# NCS_Wireless_Indicator_mcu1.net
KiCad netlist of a schematic drawn in Altium Designer
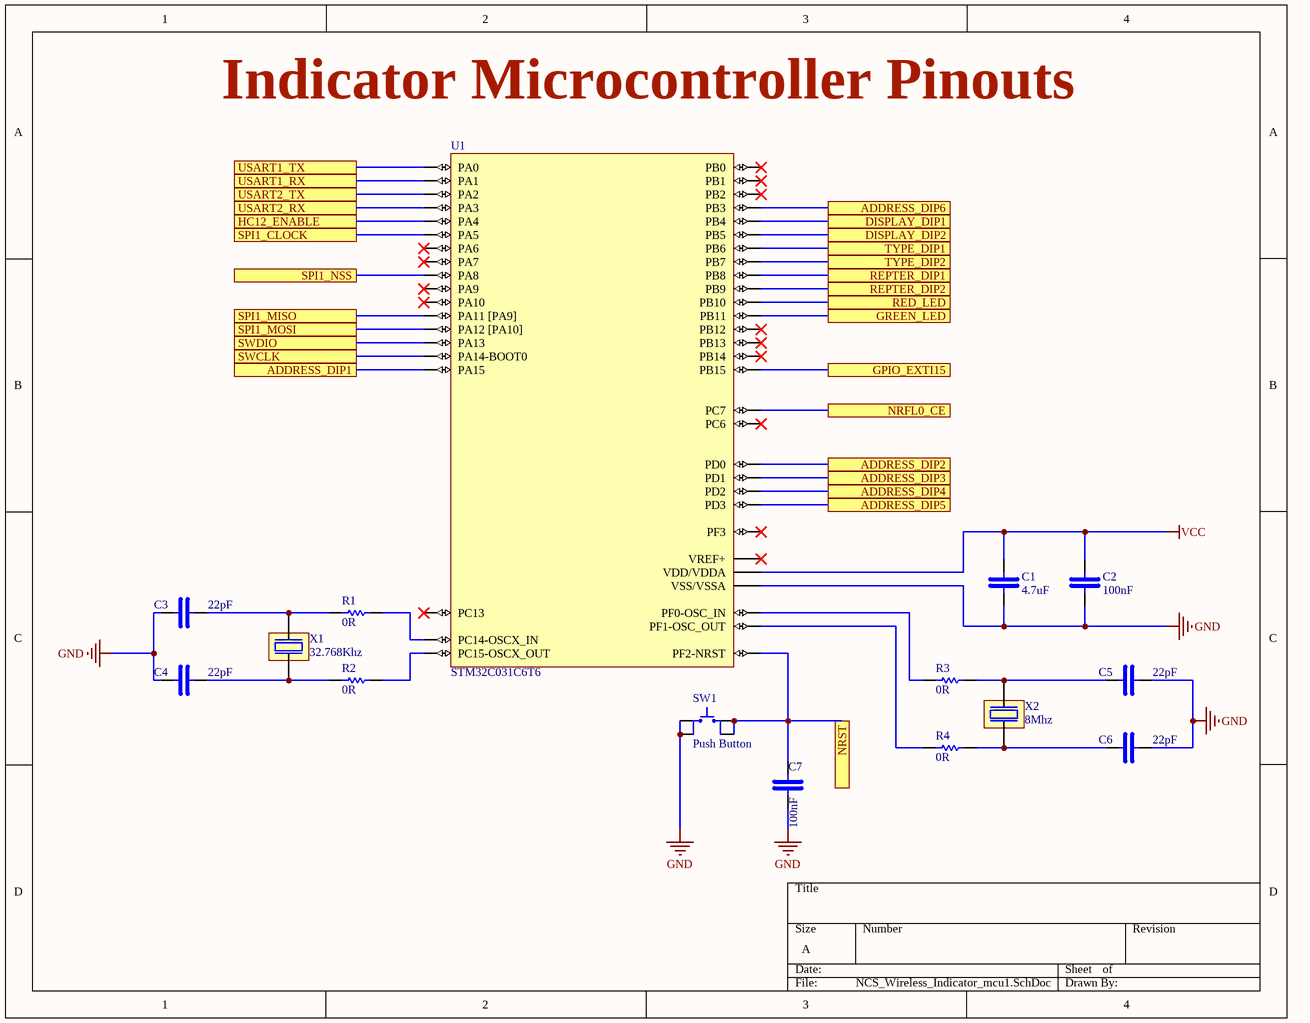
[diagram p0: NCS_Wireless_Indicator_mcu1.SchDoc]

(export (version "E")
  (design (tool "Eeschema 10.0.6"))
  (components
    (comp (ref "C1")
      (value "4.7uF")
      (footprint "C0805C209D3HACTU_2pF")
      (description "Multilayer Ceramic Capacitor, 4.7 uF, 25 V, ï¿½ 10%, X5R, 0805 [2012 Metric]")
      (fields
        (field (name "MANUFACTURER") "KEMET")
        (field (name "MANUFACTURER PART NUMBER") "C0805C475K3PACTU")
      )
      (libsource (lib "schlib") (part "C0805C475K3PACTU"))
    )
    (comp (ref "C2")
      (value "100nF")
      (footprint "C0805C104K3RACTU_100nF")
      (description "Multilayer Ceramic Capacitor, 0.1 uF, 25 V, ï¿½ 10%, X7R, 0805 [2012 Metric]")
      (fields
        (field (name "MANUFACTURER") "KEMET")
        (field (name "MANUFACTURER PART NUMBER") "C0805C104K3RACTU")
      )
      (libsource (lib "schlib") (part "C0805C104K3RACTU"))
    )
    (comp (ref "C3")
      (value "22pF")
      (footprint "C0805C209D3HACTU_2pF")
      (description "C0805C209D3HACTU_2pF")
      (fields
        (field (name "MANUFACTURER") "KEMET")
        (field (name "MANUFACTURER PART NUMBER") "C0805C209D3HACTU")
      )
      (libsource (lib "schlib") (part "C0805C209D3HACTU"))
    )
    (comp (ref "C4")
      (value "22pF")
      (footprint "C0805C209D3HACTU_2pF")
      (description "C0805C209D3HACTU_2pF")
      (fields
        (field (name "MANUFACTURER") "KEMET")
        (field (name "MANUFACTURER PART NUMBER") "C0805C209D3HACTU")
      )
      (libsource (lib "schlib") (part "C0805C209D3HACTU"))
    )
    (comp (ref "C5")
      (value "22pF")
      (footprint "C0805C209D3HACTU_2pF")
      (description "C0805C209D3HACTU_2pF")
      (fields
        (field (name "MANUFACTURER") "KEMET")
        (field (name "MANUFACTURER PART NUMBER") "C0805C209D3HACTU")
      )
      (libsource (lib "schlib") (part "C0805C209D3HACTU"))
    )
    (comp (ref "C6")
      (value "22pF")
      (footprint "C0805C209D3HACTU_2pF")
      (description "C0805C209D3HACTU_2pF")
      (fields
        (field (name "MANUFACTURER") "KEMET")
        (field (name "MANUFACTURER PART NUMBER") "C0805C209D3HACTU")
      )
      (libsource (lib "schlib") (part "C0805C209D3HACTU"))
    )
    (comp (ref "C7")
      (value "100nF")
      (footprint "C0805C104K3RACTU_100nF")
      (description "Multilayer Ceramic Capacitor, 0.1 uF, 25 V, ï¿½ 10%, X7R, 0805 [2012 Metric]")
      (fields
        (field (name "MANUFACTURER") "KEMET")
        (field (name "MANUFACTURER PART NUMBER") "C0805C104K3RACTU")
      )
      (libsource (lib "schlib") (part "C0805C104K3RACTU"))
    )
    (comp (ref "R1")
      (value "0R")
      (footprint "RC0805JR-070RL")
      (description "GENERAL PURPOSE CHIP RESISTOR Metal Glaze/thick Film, 0.125W, 0ohm, Surface Mount, 0805")
      (fields
        (field (name "MANUFACTURER") "Yageo")
        (field (name "MANUFACTURER PART NUMBER") "RC0805JR-070RL")
      )
      (libsource (lib "schlib") (part "RC0805JR-070RL"))
    )
    (comp (ref "R2")
      (value "0R")
      (footprint "RC0805JR-070RL")
      (description "GENERAL PURPOSE CHIP RESISTOR Metal Glaze/thick Film, 0.125W, 0ohm, Surface Mount, 0805")
      (fields
        (field (name "MANUFACTURER") "Yageo")
        (field (name "MANUFACTURER PART NUMBER") "RC0805JR-070RL")
      )
      (libsource (lib "schlib") (part "RC0805JR-070RL"))
    )
    (comp (ref "R3")
      (value "0R")
      (footprint "RC0805JR-070RL")
      (description "GENERAL PURPOSE CHIP RESISTOR Metal Glaze/thick Film, 0.125W, 0ohm, Surface Mount, 0805")
      (fields
        (field (name "MANUFACTURER") "Yageo")
        (field (name "MANUFACTURER PART NUMBER") "RC0805JR-070RL")
      )
      (libsource (lib "schlib") (part "RC0805JR-070RL"))
    )
    (comp (ref "R4")
      (value "0R")
      (footprint "RC0805JR-070RL")
      (description "GENERAL PURPOSE CHIP RESISTOR Metal Glaze/thick Film, 0.125W, 0ohm, Surface Mount, 0805")
      (fields
        (field (name "MANUFACTURER") "Yageo")
        (field (name "MANUFACTURER PART NUMBER") "RC0805JR-070RL")
      )
      (libsource (lib "schlib") (part "RC0805JR-070RL"))
    )
    (comp (ref "SW1")
      (value "Push Button")
      (footprint "PUSH BUTTON SMD")
      (libsource (lib "NCS_Wireless_Bed_Unit") (part "Tactile Switch SMD 4P 5.2x5.2x1.5mm - EVELTA"))
    )
    (comp (ref "U1")
      (value "STM32C031C6T6")
      (footprint "STM32C031C6T6-48N")
      (description "RISC Microcontroller, 32-Bit, FLASH, CORTEX-M4F CPU, 180MHz, CMOS, PBGA216")
      (fields (field (name "MANUFACTURER") "STMicroelectronics"))
      (libsource (lib "NCS_Wireless_Bed_Unit") (part "STM32C031C6T6"))
    )
    (comp (ref "X1")
      (value "32.768Khz")
      (footprint "32.768KHz")
      (libsource (lib "NCS_Wireless_Bed_Unit") (part "32.768 Khz RTC Crystal T38-SUNROM"))
    )
    (comp (ref "X2")
      (value "8Mhz")
      (footprint "8Mhz Crystal")
      (libsource (lib "NCS_Wireless_Bed_Unit") (part "8 Mhz Crystal HC-49US-SUNROM"))
    )
  )
  (nets
    (net (code "1") (name "/ADDRESS_DIP1") (class "Default")
      (node (ref "U1") (pin "37") (pinfunction "PA15_37") (pintype "bidirectional"))
    )
    (net (code "2") (name "/ADDRESS_DIP2") (class "Default")
      (node (ref "U1") (pin "38") (pinfunction "PD0_38") (pintype "bidirectional"))
    )
    (net (code "3") (name "/ADDRESS_DIP3") (class "Default")
      (node (ref "U1") (pin "39") (pinfunction "PD1_39") (pintype "bidirectional"))
    )
    (net (code "4") (name "/ADDRESS_DIP4") (class "Default")
      (node (ref "U1") (pin "40") (pinfunction "PD2_40") (pintype "bidirectional"))
    )
    (net (code "5") (name "/ADDRESS_DIP5") (class "Default")
      (node (ref "U1") (pin "41") (pinfunction "PD3_41") (pintype "bidirectional"))
    )
    (net (code "6") (name "/ADDRESS_DIP6") (class "Default")
      (node (ref "U1") (pin "42") (pinfunction "PB3_42") (pintype "bidirectional"))
    )
    (net (code "7") (name "/DISPLAY_DIP1") (class "Default")
      (node (ref "U1") (pin "43") (pinfunction "PB4_43") (pintype "bidirectional"))
    )
    (net (code "8") (name "/DISPLAY_DIP2") (class "Default")
      (node (ref "U1") (pin "44") (pinfunction "PB5_44") (pintype "bidirectional"))
    )
    (net (code "9") (name "/GPIO_EXTI15") (class "Default")
      (node (ref "U1") (pin "27") (pinfunction "PB15_27") (pintype "bidirectional"))
    )
    (net (code "10") (name "/GREEN_LED") (class "Default")
      (node (ref "U1") (pin "23") (pinfunction "PB11_23") (pintype "bidirectional"))
    )
    (net (code "11") (name "/HC12_ENABLE") (class "Default")
      (node (ref "U1") (pin "15") (pinfunction "PA4_15") (pintype "bidirectional"))
    )
    (net (code "12") (name "/NRFL0_CE") (class "Default")
      (node (ref "U1") (pin "31") (pinfunction "PC7_31") (pintype "bidirectional"))
    )
    (net (code "13") (name "/NRST") (class "Default")
      (node (ref "C7") (pin "2") (pinfunction "2_2") (pintype "passive"))
      (node (ref "SW1") (pin "3") (pinfunction "3_3") (pintype "passive"))
      (node (ref "SW1") (pin "4") (pinfunction "4_4") (pintype "passive"))
      (node (ref "U1") (pin "10") (pinfunction "PF2-NRST_10") (pintype "bidirectional"))
    )
    (net (code "14") (name "/RED_LED") (class "Default")
      (node (ref "U1") (pin "22") (pinfunction "PB10_22") (pintype "bidirectional"))
    )
    (net (code "15") (name "/REPTER_DIP1") (class "Default")
      (node (ref "U1") (pin "47") (pinfunction "PB8_47") (pintype "bidirectional"))
    )
    (net (code "16") (name "/REPTER_DIP2") (class "Default")
      (node (ref "U1") (pin "48") (pinfunction "PB9_48") (pintype "bidirectional"))
    )
    (net (code "17") (name "/SPI1_CLOCK") (class "Default")
      (node (ref "U1") (pin "16") (pinfunction "PA5_16") (pintype "bidirectional"))
    )
    (net (code "18") (name "/SPI1_MISO") (class "Default")
      (node (ref "U1") (pin "33") (pinfunction "PA11_[PA9]_33") (pintype "bidirectional"))
    )
    (net (code "19") (name "/SPI1_MOSI") (class "Default")
      (node (ref "U1") (pin "34") (pinfunction "PA12_[PA10]_34") (pintype "bidirectional"))
    )
    (net (code "20") (name "/SPI1_NSS") (class "Default")
      (node (ref "U1") (pin "28") (pinfunction "PA8_28") (pintype "bidirectional"))
    )
    (net (code "21") (name "/SWCLK") (class "Default")
      (node (ref "U1") (pin "36") (pinfunction "PA14-BOOT0_36") (pintype "bidirectional"))
    )
    (net (code "22") (name "/SWDIO") (class "Default")
      (node (ref "U1") (pin "35") (pinfunction "PA13_35") (pintype "bidirectional"))
    )
    (net (code "23") (name "/TYPE_DIP1") (class "Default")
      (node (ref "U1") (pin "45") (pinfunction "PB6_45") (pintype "bidirectional"))
    )
    (net (code "24") (name "/TYPE_DIP2") (class "Default")
      (node (ref "U1") (pin "46") (pinfunction "PB7_46") (pintype "bidirectional"))
    )
    (net (code "25") (name "/USART1_RX") (class "Default")
      (node (ref "U1") (pin "12") (pinfunction "PA1_12") (pintype "bidirectional"))
    )
    (net (code "26") (name "/USART1_TX") (class "Default")
      (node (ref "U1") (pin "11") (pinfunction "PA0_11") (pintype "bidirectional"))
    )
    (net (code "27") (name "/USART2_RX") (class "Default")
      (node (ref "U1") (pin "14") (pinfunction "PA3_14") (pintype "bidirectional"))
    )
    (net (code "28") (name "/USART2_TX") (class "Default")
      (node (ref "U1") (pin "13") (pinfunction "PA2_13") (pintype "bidirectional"))
    )
    (net (code "29") (name "GND") (class "Default")
      (node (ref "C1") (pin "1") (pinfunction "1_1") (pintype "passive"))
      (node (ref "C2") (pin "1") (pinfunction "1_1") (pintype "passive"))
      (node (ref "C3") (pin "2") (pinfunction "2_2") (pintype "passive"))
      (node (ref "C4") (pin "2") (pinfunction "2_2") (pintype "passive"))
      (node (ref "C5") (pin "1") (pinfunction "1_1") (pintype "passive"))
      (node (ref "C6") (pin "1") (pinfunction "1_1") (pintype "passive"))
      (node (ref "C7") (pin "1") (pinfunction "1_1") (pintype "passive"))
      (node (ref "SW1") (pin "1") (pinfunction "1_1") (pintype "passive"))
      (node (ref "SW1") (pin "2") (pinfunction "2_2") (pintype "passive"))
      (node (ref "U1") (pin "7") (pinfunction "VSS/VSSA_7") (pintype "power_in"))
    )
    (net (code "30") (name "Net-(C3-Pad1)") (class "Default")
      (node (ref "C3") (pin "1") (pinfunction "1_1") (pintype "passive"))
      (node (ref "R1") (pin "1") (pinfunction "1_1") (pintype "passive"))
      (node (ref "X1") (pin "2") (pinfunction "2_2") (pintype "passive"))
    )
    (net (code "31") (name "Net-(C4-Pad1)") (class "Default")
      (node (ref "C4") (pin "1") (pinfunction "1_1") (pintype "passive"))
      (node (ref "R2") (pin "1") (pinfunction "1_1") (pintype "passive"))
      (node (ref "X1") (pin "1") (pinfunction "1_1") (pintype "passive"))
    )
    (net (code "32") (name "Net-(C5-Pad2)") (class "Default")
      (node (ref "C5") (pin "2") (pinfunction "2_2") (pintype "passive"))
      (node (ref "R3") (pin "2") (pinfunction "2_2") (pintype "passive"))
      (node (ref "X2") (pin "2") (pinfunction "2_2") (pintype "passive"))
    )
    (net (code "33") (name "Net-(C6-Pad2)") (class "Default")
      (node (ref "C6") (pin "2") (pinfunction "2_2") (pintype "passive"))
      (node (ref "R4") (pin "2") (pinfunction "2_2") (pintype "passive"))
      (node (ref "X2") (pin "1") (pinfunction "1_1") (pintype "passive"))
    )
    (net (code "34") (name "Net-(U1-PC14-OSCX_IN)") (class "Default")
      (node (ref "R1") (pin "2") (pinfunction "2_2") (pintype "passive"))
      (node (ref "U1") (pin "2") (pinfunction "PC14-OSCX_IN_2") (pintype "bidirectional"))
    )
    (net (code "35") (name "Net-(U1-PC15-OSCX_OUT)") (class "Default")
      (node (ref "R2") (pin "2") (pinfunction "2_2") (pintype "passive"))
      (node (ref "U1") (pin "3") (pinfunction "PC15-OSCX_OUT_3") (pintype "bidirectional"))
    )
    (net (code "36") (name "Net-(U1-PF0-OSC_IN)") (class "Default")
      (node (ref "R3") (pin "1") (pinfunction "1_1") (pintype "passive"))
      (node (ref "U1") (pin "8") (pinfunction "PF0-OSC_IN_8") (pintype "bidirectional"))
    )
    (net (code "37") (name "Net-(U1-PF1-OSC_OUT)") (class "Default")
      (node (ref "R4") (pin "1") (pinfunction "1_1") (pintype "passive"))
      (node (ref "U1") (pin "9") (pinfunction "PF1-OSC_OUT_9") (pintype "bidirectional"))
    )
    (net (code "38") (name "VCC") (class "Default")
      (node (ref "C1") (pin "2") (pinfunction "2_2") (pintype "passive"))
      (node (ref "C2") (pin "2") (pinfunction "2_2") (pintype "passive"))
      (node (ref "U1") (pin "6") (pinfunction "VDD/VDDA_6") (pintype "power_in"))
    )
    (net (code "39") (name "unconnected-(U1-PA6-Pad17)") (class "Default")
      (node (ref "U1") (pin "17") (pinfunction "PA6_17") (pintype "bidirectional+no_connect"))
    )
    (net (code "40") (name "unconnected-(U1-PA7-Pad18)") (class "Default")
      (node (ref "U1") (pin "18") (pinfunction "PA7_18") (pintype "bidirectional+no_connect"))
    )
    (net (code "41") (name "unconnected-(U1-PA9-Pad29)") (class "Default")
      (node (ref "U1") (pin "29") (pinfunction "PA9_29") (pintype "bidirectional+no_connect"))
    )
    (net (code "42") (name "unconnected-(U1-PA10-Pad32)") (class "Default")
      (node (ref "U1") (pin "32") (pinfunction "PA10_32") (pintype "bidirectional+no_connect"))
    )
    (net (code "43") (name "unconnected-(U1-PB0-Pad19)") (class "Default")
      (node (ref "U1") (pin "19") (pinfunction "PB0_19") (pintype "bidirectional+no_connect"))
    )
    (net (code "44") (name "unconnected-(U1-PB1-Pad20)") (class "Default")
      (node (ref "U1") (pin "20") (pinfunction "PB1_20") (pintype "bidirectional+no_connect"))
    )
    (net (code "45") (name "unconnected-(U1-PB2-Pad21)") (class "Default")
      (node (ref "U1") (pin "21") (pinfunction "PB2_21") (pintype "bidirectional+no_connect"))
    )
    (net (code "46") (name "unconnected-(U1-PB12-Pad24)") (class "Default")
      (node (ref "U1") (pin "24") (pinfunction "PB12_24") (pintype "bidirectional+no_connect"))
    )
    (net (code "47") (name "unconnected-(U1-PB13-Pad25)") (class "Default")
      (node (ref "U1") (pin "25") (pinfunction "PB13_25") (pintype "bidirectional+no_connect"))
    )
    (net (code "48") (name "unconnected-(U1-PB14-Pad26)") (class "Default")
      (node (ref "U1") (pin "26") (pinfunction "PB14_26") (pintype "bidirectional+no_connect"))
    )
    (net (code "49") (name "unconnected-(U1-PC6-Pad30)") (class "Default")
      (node (ref "U1") (pin "30") (pinfunction "PC6_30") (pintype "bidirectional+no_connect"))
    )
    (net (code "50") (name "unconnected-(U1-PC13-Pad1)") (class "Default")
      (node (ref "U1") (pin "1") (pinfunction "PC13_1") (pintype "bidirectional+no_connect"))
    )
    (net (code "51") (name "unconnected-(U1-PF3-Pad4)") (class "Default")
      (node (ref "U1") (pin "4") (pinfunction "PF3_4") (pintype "bidirectional+no_connect"))
    )
    (net (code "52") (name "unconnected-(U1-VREF+-Pad5)") (class "Default")
      (node (ref "U1") (pin "5") (pinfunction "VREF+_5") (pintype "power_in+no_connect"))
    )
  )
)
